# 5853-top-board.net
KiCad netlist of a schematic drawn in EAGLE
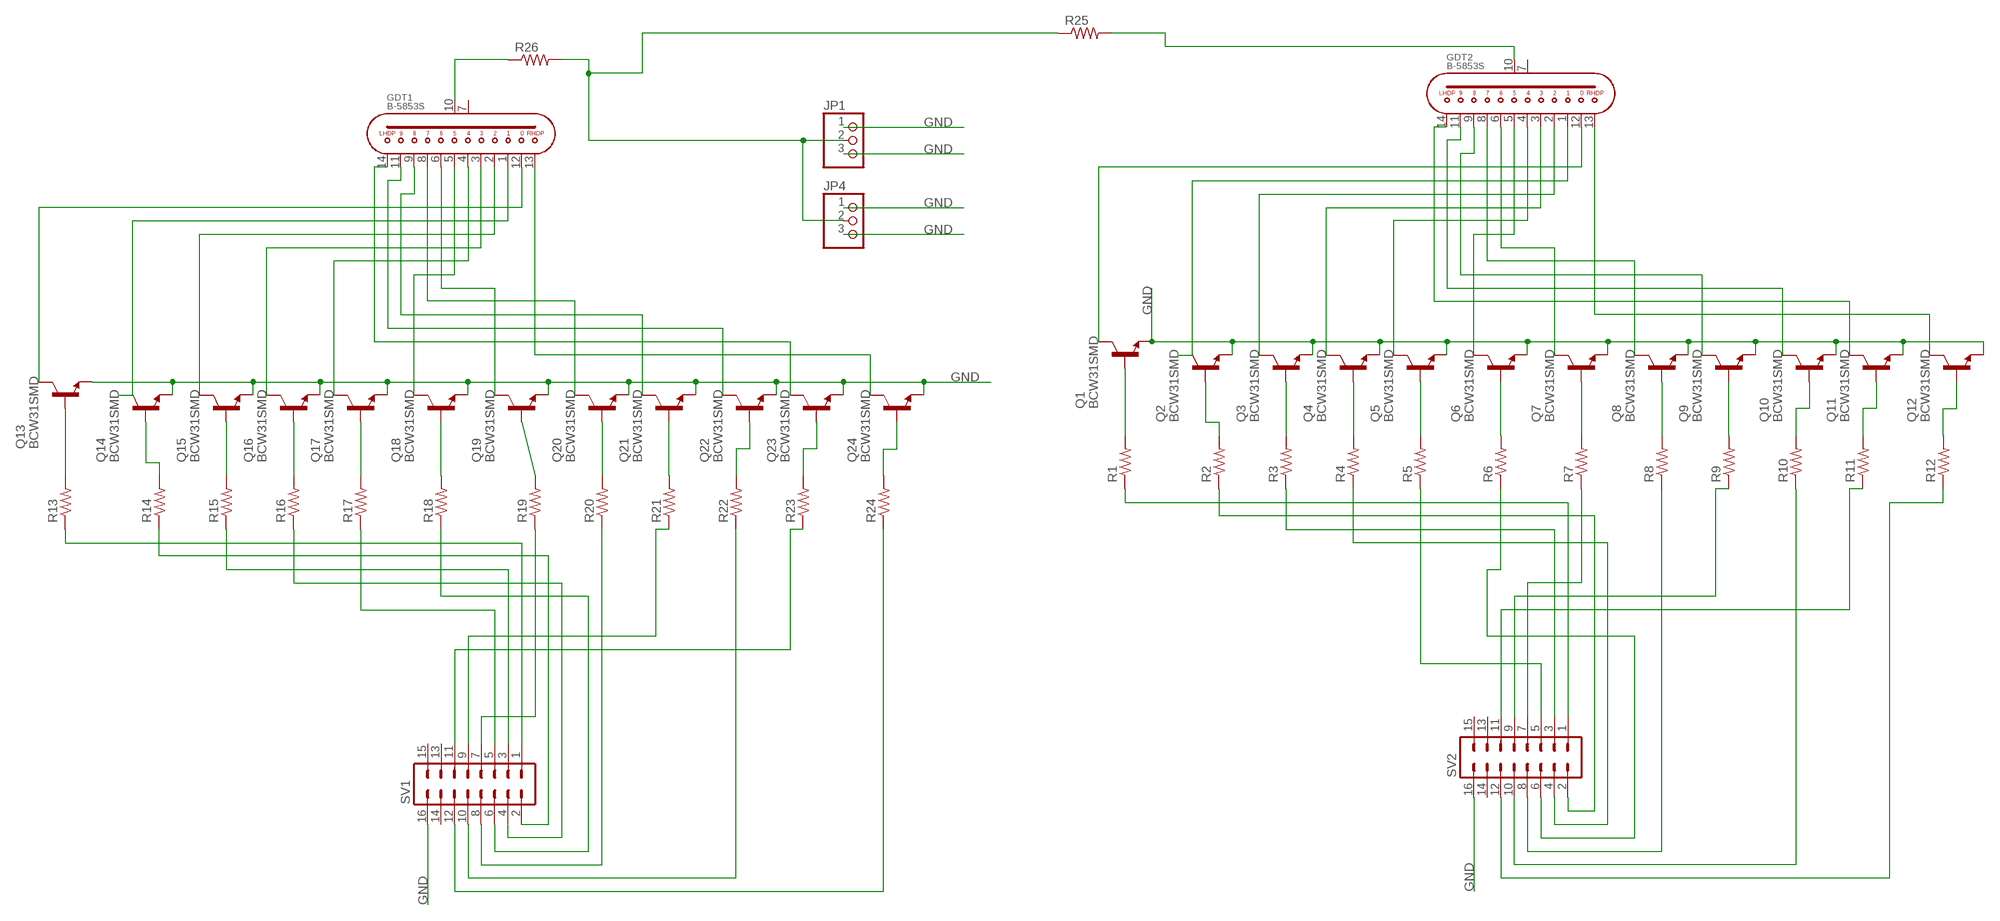
[diagram p0: schematic, sheet 1]

(export (version "E")
  (design (tool "Eeschema 10.0.6"))
  (components
    (comp (ref "GDT1")
      (value "B-5853S")
      (footprint "eagle-import:SK-207")
      (libsource (lib "eagle-import") (part "B-5853S"))
    )
    (comp (ref "GDT2")
      (value "B-5853S")
      (footprint "eagle-import:SK-207")
      (libsource (lib "eagle-import") (part "B-5853S"))
    )
    (comp (ref "JP1")
      (value "PINHD-1X3")
      (footprint "eagle-import:1X03")
      (libsource (lib "eagle-import") (part "PINHD-1X3"))
    )
    (comp (ref "JP4")
      (value "PINHD-1X3")
      (footprint "eagle-import:1X03")
      (libsource (lib "eagle-import") (part "PINHD-1X3"))
    )
    (comp (ref "Q1")
      (value "BCW31SMD")
      (footprint "eagle-import:SOT23-BEC")
      (libsource (lib "eagle-import") (part "BCW31SMD"))
    )
    (comp (ref "Q2")
      (value "BCW31SMD")
      (footprint "eagle-import:SOT23-BEC")
      (libsource (lib "eagle-import") (part "BCW31SMD"))
    )
    (comp (ref "Q3")
      (value "BCW31SMD")
      (footprint "eagle-import:SOT23-BEC")
      (libsource (lib "eagle-import") (part "BCW31SMD"))
    )
    (comp (ref "Q4")
      (value "BCW31SMD")
      (footprint "eagle-import:SOT23-BEC")
      (libsource (lib "eagle-import") (part "BCW31SMD"))
    )
    (comp (ref "Q5")
      (value "BCW31SMD")
      (footprint "eagle-import:SOT23-BEC")
      (libsource (lib "eagle-import") (part "BCW31SMD"))
    )
    (comp (ref "Q6")
      (value "BCW31SMD")
      (footprint "eagle-import:SOT23-BEC")
      (libsource (lib "eagle-import") (part "BCW31SMD"))
    )
    (comp (ref "Q7")
      (value "BCW31SMD")
      (footprint "eagle-import:SOT23-BEC")
      (libsource (lib "eagle-import") (part "BCW31SMD"))
    )
    (comp (ref "Q8")
      (value "BCW31SMD")
      (footprint "eagle-import:SOT23-BEC")
      (libsource (lib "eagle-import") (part "BCW31SMD"))
    )
    (comp (ref "Q9")
      (value "BCW31SMD")
      (footprint "eagle-import:SOT23-BEC")
      (libsource (lib "eagle-import") (part "BCW31SMD"))
    )
    (comp (ref "Q10")
      (value "BCW31SMD")
      (footprint "eagle-import:SOT23-BEC")
      (libsource (lib "eagle-import") (part "BCW31SMD"))
    )
    (comp (ref "Q11")
      (value "BCW31SMD")
      (footprint "eagle-import:SOT23-BEC")
      (libsource (lib "eagle-import") (part "BCW31SMD"))
    )
    (comp (ref "Q12")
      (value "BCW31SMD")
      (footprint "eagle-import:SOT23-BEC")
      (libsource (lib "eagle-import") (part "BCW31SMD"))
    )
    (comp (ref "Q13")
      (value "BCW31SMD")
      (footprint "eagle-import:SOT23-BEC")
      (libsource (lib "eagle-import") (part "BCW31SMD"))
    )
    (comp (ref "Q14")
      (value "BCW31SMD")
      (footprint "eagle-import:SOT23-BEC")
      (libsource (lib "eagle-import") (part "BCW31SMD"))
    )
    (comp (ref "Q15")
      (value "BCW31SMD")
      (footprint "eagle-import:SOT23-BEC")
      (libsource (lib "eagle-import") (part "BCW31SMD"))
    )
    (comp (ref "Q16")
      (value "BCW31SMD")
      (footprint "eagle-import:SOT23-BEC")
      (libsource (lib "eagle-import") (part "BCW31SMD"))
    )
    (comp (ref "Q17")
      (value "BCW31SMD")
      (footprint "eagle-import:SOT23-BEC")
      (libsource (lib "eagle-import") (part "BCW31SMD"))
    )
    (comp (ref "Q18")
      (value "BCW31SMD")
      (footprint "eagle-import:SOT23-BEC")
      (libsource (lib "eagle-import") (part "BCW31SMD"))
    )
    (comp (ref "Q19")
      (value "BCW31SMD")
      (footprint "eagle-import:SOT23-BEC")
      (libsource (lib "eagle-import") (part "BCW31SMD"))
    )
    (comp (ref "Q20")
      (value "BCW31SMD")
      (footprint "eagle-import:SOT23-BEC")
      (libsource (lib "eagle-import") (part "BCW31SMD"))
    )
    (comp (ref "Q21")
      (value "BCW31SMD")
      (footprint "eagle-import:SOT23-BEC")
      (libsource (lib "eagle-import") (part "BCW31SMD"))
    )
    (comp (ref "Q22")
      (value "BCW31SMD")
      (footprint "eagle-import:SOT23-BEC")
      (libsource (lib "eagle-import") (part "BCW31SMD"))
    )
    (comp (ref "Q23")
      (value "BCW31SMD")
      (footprint "eagle-import:SOT23-BEC")
      (libsource (lib "eagle-import") (part "BCW31SMD"))
    )
    (comp (ref "Q24")
      (value "BCW31SMD")
      (footprint "eagle-import:SOT23-BEC")
      (libsource (lib "eagle-import") (part "BCW31SMD"))
    )
    (comp (ref "R1")
      (value "R-US_M0805")
      (footprint "eagle-import:M0805")
      (libsource (lib "eagle-import") (part "R-US_M0805"))
    )
    (comp (ref "R2")
      (value "R-US_M0805")
      (footprint "eagle-import:M0805")
      (libsource (lib "eagle-import") (part "R-US_M0805"))
    )
    (comp (ref "R3")
      (value "R-US_M0805")
      (footprint "eagle-import:M0805")
      (libsource (lib "eagle-import") (part "R-US_M0805"))
    )
    (comp (ref "R4")
      (value "R-US_M0805")
      (footprint "eagle-import:M0805")
      (libsource (lib "eagle-import") (part "R-US_M0805"))
    )
    (comp (ref "R5")
      (value "R-US_M0805")
      (footprint "eagle-import:M0805")
      (libsource (lib "eagle-import") (part "R-US_M0805"))
    )
    (comp (ref "R6")
      (value "R-US_M0805")
      (footprint "eagle-import:M0805")
      (libsource (lib "eagle-import") (part "R-US_M0805"))
    )
    (comp (ref "R7")
      (value "R-US_M0805")
      (footprint "eagle-import:M0805")
      (libsource (lib "eagle-import") (part "R-US_M0805"))
    )
    (comp (ref "R8")
      (value "R-US_M0805")
      (footprint "eagle-import:M0805")
      (libsource (lib "eagle-import") (part "R-US_M0805"))
    )
    (comp (ref "R9")
      (value "R-US_M0805")
      (footprint "eagle-import:M0805")
      (libsource (lib "eagle-import") (part "R-US_M0805"))
    )
    (comp (ref "R10")
      (value "R-US_M0805")
      (footprint "eagle-import:M0805")
      (libsource (lib "eagle-import") (part "R-US_M0805"))
    )
    (comp (ref "R11")
      (value "R-US_M0805")
      (footprint "eagle-import:M0805")
      (libsource (lib "eagle-import") (part "R-US_M0805"))
    )
    (comp (ref "R12")
      (value "R-US_M0805")
      (footprint "eagle-import:M0805")
      (libsource (lib "eagle-import") (part "R-US_M0805"))
    )
    (comp (ref "R13")
      (value "R-US_M0805")
      (footprint "eagle-import:M0805")
      (libsource (lib "eagle-import") (part "R-US_M0805"))
    )
    (comp (ref "R14")
      (value "R-US_M0805")
      (footprint "eagle-import:M0805")
      (libsource (lib "eagle-import") (part "R-US_M0805"))
    )
    (comp (ref "R15")
      (value "R-US_M0805")
      (footprint "eagle-import:M0805")
      (libsource (lib "eagle-import") (part "R-US_M0805"))
    )
    (comp (ref "R16")
      (value "R-US_M0805")
      (footprint "eagle-import:M0805")
      (libsource (lib "eagle-import") (part "R-US_M0805"))
    )
    (comp (ref "R17")
      (value "R-US_M0805")
      (footprint "eagle-import:M0805")
      (libsource (lib "eagle-import") (part "R-US_M0805"))
    )
    (comp (ref "R18")
      (value "R-US_M0805")
      (footprint "eagle-import:M0805")
      (libsource (lib "eagle-import") (part "R-US_M0805"))
    )
    (comp (ref "R19")
      (value "R-US_M0805")
      (footprint "eagle-import:M0805")
      (libsource (lib "eagle-import") (part "R-US_M0805"))
    )
    (comp (ref "R20")
      (value "R-US_M0805")
      (footprint "eagle-import:M0805")
      (libsource (lib "eagle-import") (part "R-US_M0805"))
    )
    (comp (ref "R21")
      (value "R-US_M0805")
      (footprint "eagle-import:M0805")
      (libsource (lib "eagle-import") (part "R-US_M0805"))
    )
    (comp (ref "R22")
      (value "R-US_M0805")
      (footprint "eagle-import:M0805")
      (libsource (lib "eagle-import") (part "R-US_M0805"))
    )
    (comp (ref "R23")
      (value "R-US_M0805")
      (footprint "eagle-import:M0805")
      (libsource (lib "eagle-import") (part "R-US_M0805"))
    )
    (comp (ref "R24")
      (value "R-US_M0805")
      (footprint "eagle-import:M0805")
      (libsource (lib "eagle-import") (part "R-US_M0805"))
    )
    (comp (ref "R25")
      (value "R-US_M0805")
      (footprint "eagle-import:M0805")
      (libsource (lib "eagle-import") (part "R-US_M0805"))
    )
    (comp (ref "R26")
      (value "R-US_M0805")
      (footprint "eagle-import:M0805")
      (libsource (lib "eagle-import") (part "R-US_M0805"))
    )
    (comp (ref "SV1")
      (value "ML16")
      (footprint "eagle-import:ML16")
      (libsource (lib "eagle-import") (part "ML16"))
    )
    (comp (ref "SV2")
      (value "ML16")
      (footprint "eagle-import:ML16")
      (libsource (lib "eagle-import") (part "ML16"))
    )
  )
  (nets
    (net (code "1") (name "/GND") (class "Default")
      (node (ref "JP1") (pin "1") (pinfunction "1_1") (pintype "passive"))
      (node (ref "JP1") (pin "3") (pinfunction "3_3") (pintype "passive"))
      (node (ref "JP4") (pin "1") (pinfunction "1_1") (pintype "passive"))
      (node (ref "JP4") (pin "3") (pinfunction "3_3") (pintype "passive"))
      (node (ref "Q1") (pin "E") (pinfunction "E_E") (pintype "passive"))
      (node (ref "Q10") (pin "E") (pinfunction "E_E") (pintype "passive"))
      (node (ref "Q11") (pin "E") (pinfunction "E_E") (pintype "passive"))
      (node (ref "Q12") (pin "E") (pinfunction "E_E") (pintype "passive"))
      (node (ref "Q13") (pin "E") (pinfunction "E_E") (pintype "passive"))
      (node (ref "Q14") (pin "E") (pinfunction "E_E") (pintype "passive"))
      (node (ref "Q15") (pin "E") (pinfunction "E_E") (pintype "passive"))
      (node (ref "Q16") (pin "E") (pinfunction "E_E") (pintype "passive"))
      (node (ref "Q17") (pin "E") (pinfunction "E_E") (pintype "passive"))
      (node (ref "Q18") (pin "E") (pinfunction "E_E") (pintype "passive"))
      (node (ref "Q19") (pin "E") (pinfunction "E_E") (pintype "passive"))
      (node (ref "Q2") (pin "E") (pinfunction "E_E") (pintype "passive"))
      (node (ref "Q20") (pin "E") (pinfunction "E_E") (pintype "passive"))
      (node (ref "Q21") (pin "E") (pinfunction "E_E") (pintype "passive"))
      (node (ref "Q22") (pin "E") (pinfunction "E_E") (pintype "passive"))
      (node (ref "Q23") (pin "E") (pinfunction "E_E") (pintype "passive"))
      (node (ref "Q24") (pin "E") (pinfunction "E_E") (pintype "passive"))
      (node (ref "Q3") (pin "E") (pinfunction "E_E") (pintype "passive"))
      (node (ref "Q4") (pin "E") (pinfunction "E_E") (pintype "passive"))
      (node (ref "Q5") (pin "E") (pinfunction "E_E") (pintype "passive"))
      (node (ref "Q6") (pin "E") (pinfunction "E_E") (pintype "passive"))
      (node (ref "Q7") (pin "E") (pinfunction "E_E") (pintype "passive"))
      (node (ref "Q8") (pin "E") (pinfunction "E_E") (pintype "passive"))
      (node (ref "Q9") (pin "E") (pinfunction "E_E") (pintype "passive"))
      (node (ref "SV1") (pin "16") (pinfunction "16_16") (pintype "passive"))
      (node (ref "SV2") (pin "16") (pinfunction "16_16") (pintype "passive"))
    )
    (net (code "2") (name "Net-(GDT1-Pad1)") (class "Default")
      (node (ref "GDT1") (pin "1") (pinfunction "1_1") (pintype "passive"))
      (node (ref "Q14") (pin "C") (pinfunction "C_C") (pintype "passive"))
    )
    (net (code "3") (name "Net-(GDT1-Pad2)") (class "Default")
      (node (ref "GDT1") (pin "2") (pinfunction "2_2") (pintype "passive"))
      (node (ref "Q15") (pin "C") (pinfunction "C_C") (pintype "passive"))
    )
    (net (code "4") (name "Net-(GDT1-Pad3)") (class "Default")
      (node (ref "GDT1") (pin "3") (pinfunction "3_3") (pintype "passive"))
      (node (ref "Q16") (pin "C") (pinfunction "C_C") (pintype "passive"))
    )
    (net (code "5") (name "Net-(GDT1-Pad4)") (class "Default")
      (node (ref "GDT1") (pin "4") (pinfunction "4_4") (pintype "passive"))
      (node (ref "Q17") (pin "C") (pinfunction "C_C") (pintype "passive"))
    )
    (net (code "6") (name "Net-(GDT1-Pad5)") (class "Default")
      (node (ref "GDT1") (pin "5") (pinfunction "5_5") (pintype "passive"))
      (node (ref "Q18") (pin "C") (pinfunction "C_C") (pintype "passive"))
    )
    (net (code "7") (name "Net-(GDT1-Pad6)") (class "Default")
      (node (ref "GDT1") (pin "6") (pinfunction "6_6") (pintype "passive"))
      (node (ref "Q19") (pin "C") (pinfunction "C_C") (pintype "passive"))
    )
    (net (code "8") (name "Net-(GDT1-Pad8)") (class "Default")
      (node (ref "GDT1") (pin "8") (pinfunction "8_8") (pintype "passive"))
      (node (ref "Q20") (pin "C") (pinfunction "C_C") (pintype "passive"))
    )
    (net (code "9") (name "Net-(GDT1-Pad9)") (class "Default")
      (node (ref "GDT1") (pin "9") (pinfunction "9_9") (pintype "passive"))
      (node (ref "Q21") (pin "C") (pinfunction "C_C") (pintype "passive"))
    )
    (net (code "10") (name "Net-(GDT1-Pad10)") (class "Default")
      (node (ref "GDT1") (pin "10") (pinfunction "10_10") (pintype "passive"))
      (node (ref "R26") (pin "1") (pinfunction "1_1") (pintype "passive"))
    )
    (net (code "11") (name "Net-(GDT1-Pad11)") (class "Default")
      (node (ref "GDT1") (pin "11") (pinfunction "11_11") (pintype "passive"))
      (node (ref "Q22") (pin "C") (pinfunction "C_C") (pintype "passive"))
    )
    (net (code "12") (name "Net-(GDT1-Pad12)") (class "Default")
      (node (ref "GDT1") (pin "12") (pinfunction "12_12") (pintype "passive"))
      (node (ref "Q13") (pin "C") (pinfunction "C_C") (pintype "passive"))
    )
    (net (code "13") (name "Net-(GDT1-Pad13)") (class "Default")
      (node (ref "GDT1") (pin "13") (pinfunction "13_13") (pintype "passive"))
      (node (ref "Q24") (pin "C") (pinfunction "C_C") (pintype "passive"))
    )
    (net (code "14") (name "Net-(GDT1-Pad14)") (class "Default")
      (node (ref "GDT1") (pin "14") (pinfunction "14_14") (pintype "passive"))
      (node (ref "Q23") (pin "C") (pinfunction "C_C") (pintype "passive"))
    )
    (net (code "15") (name "Net-(GDT2-Pad1)") (class "Default")
      (node (ref "GDT2") (pin "1") (pinfunction "1_1") (pintype "passive"))
      (node (ref "Q2") (pin "C") (pinfunction "C_C") (pintype "passive"))
    )
    (net (code "16") (name "Net-(GDT2-Pad2)") (class "Default")
      (node (ref "GDT2") (pin "2") (pinfunction "2_2") (pintype "passive"))
      (node (ref "Q3") (pin "C") (pinfunction "C_C") (pintype "passive"))
    )
    (net (code "17") (name "Net-(GDT2-Pad3)") (class "Default")
      (node (ref "GDT2") (pin "3") (pinfunction "3_3") (pintype "passive"))
      (node (ref "Q4") (pin "C") (pinfunction "C_C") (pintype "passive"))
    )
    (net (code "18") (name "Net-(GDT2-Pad4)") (class "Default")
      (node (ref "GDT2") (pin "4") (pinfunction "4_4") (pintype "passive"))
      (node (ref "Q5") (pin "C") (pinfunction "C_C") (pintype "passive"))
    )
    (net (code "19") (name "Net-(GDT2-Pad5)") (class "Default")
      (node (ref "GDT2") (pin "5") (pinfunction "5_5") (pintype "passive"))
      (node (ref "Q6") (pin "C") (pinfunction "C_C") (pintype "passive"))
    )
    (net (code "20") (name "Net-(GDT2-Pad6)") (class "Default")
      (node (ref "GDT2") (pin "6") (pinfunction "6_6") (pintype "passive"))
      (node (ref "Q7") (pin "C") (pinfunction "C_C") (pintype "passive"))
    )
    (net (code "21") (name "Net-(GDT2-Pad8)") (class "Default")
      (node (ref "GDT2") (pin "8") (pinfunction "8_8") (pintype "passive"))
      (node (ref "Q8") (pin "C") (pinfunction "C_C") (pintype "passive"))
    )
    (net (code "22") (name "Net-(GDT2-Pad9)") (class "Default")
      (node (ref "GDT2") (pin "9") (pinfunction "9_9") (pintype "passive"))
      (node (ref "Q9") (pin "C") (pinfunction "C_C") (pintype "passive"))
    )
    (net (code "23") (name "Net-(GDT2-Pad10)") (class "Default")
      (node (ref "GDT2") (pin "10") (pinfunction "10_10") (pintype "passive"))
      (node (ref "R25") (pin "2") (pinfunction "2_2") (pintype "passive"))
    )
    (net (code "24") (name "Net-(GDT2-Pad11)") (class "Default")
      (node (ref "GDT2") (pin "11") (pinfunction "11_11") (pintype "passive"))
      (node (ref "Q10") (pin "C") (pinfunction "C_C") (pintype "passive"))
    )
    (net (code "25") (name "Net-(GDT2-Pad12)") (class "Default")
      (node (ref "GDT2") (pin "12") (pinfunction "12_12") (pintype "passive"))
      (node (ref "Q1") (pin "C") (pinfunction "C_C") (pintype "passive"))
    )
    (net (code "26") (name "Net-(GDT2-Pad13)") (class "Default")
      (node (ref "GDT2") (pin "13") (pinfunction "13_13") (pintype "passive"))
      (node (ref "Q12") (pin "C") (pinfunction "C_C") (pintype "passive"))
    )
    (net (code "27") (name "Net-(GDT2-Pad14)") (class "Default")
      (node (ref "GDT2") (pin "14") (pinfunction "14_14") (pintype "passive"))
      (node (ref "Q11") (pin "C") (pinfunction "C_C") (pintype "passive"))
    )
    (net (code "28") (name "Net-(JP1-Pad2)") (class "Default")
      (node (ref "JP1") (pin "2") (pinfunction "2_2") (pintype "passive"))
      (node (ref "JP4") (pin "2") (pinfunction "2_2") (pintype "passive"))
      (node (ref "R25") (pin "1") (pinfunction "1_1") (pintype "passive"))
      (node (ref "R26") (pin "2") (pinfunction "2_2") (pintype "passive"))
    )
    (net (code "29") (name "Net-(Q1-PadB)") (class "Default")
      (node (ref "Q1") (pin "B") (pinfunction "B_B") (pintype "passive"))
      (node (ref "R1") (pin "2") (pinfunction "2_2") (pintype "passive"))
    )
    (net (code "30") (name "Net-(Q2-PadB)") (class "Default")
      (node (ref "Q2") (pin "B") (pinfunction "B_B") (pintype "passive"))
      (node (ref "R2") (pin "2") (pinfunction "2_2") (pintype "passive"))
    )
    (net (code "31") (name "Net-(Q3-PadB)") (class "Default")
      (node (ref "Q3") (pin "B") (pinfunction "B_B") (pintype "passive"))
      (node (ref "R3") (pin "2") (pinfunction "2_2") (pintype "passive"))
    )
    (net (code "32") (name "Net-(Q4-PadB)") (class "Default")
      (node (ref "Q4") (pin "B") (pinfunction "B_B") (pintype "passive"))
      (node (ref "R4") (pin "2") (pinfunction "2_2") (pintype "passive"))
    )
    (net (code "33") (name "Net-(Q5-PadB)") (class "Default")
      (node (ref "Q5") (pin "B") (pinfunction "B_B") (pintype "passive"))
      (node (ref "R5") (pin "2") (pinfunction "2_2") (pintype "passive"))
    )
    (net (code "34") (name "Net-(Q6-PadB)") (class "Default")
      (node (ref "Q6") (pin "B") (pinfunction "B_B") (pintype "passive"))
      (node (ref "R6") (pin "2") (pinfunction "2_2") (pintype "passive"))
    )
    (net (code "35") (name "Net-(Q7-PadB)") (class "Default")
      (node (ref "Q7") (pin "B") (pinfunction "B_B") (pintype "passive"))
      (node (ref "R7") (pin "2") (pinfunction "2_2") (pintype "passive"))
    )
    (net (code "36") (name "Net-(Q8-PadB)") (class "Default")
      (node (ref "Q8") (pin "B") (pinfunction "B_B") (pintype "passive"))
      (node (ref "R8") (pin "2") (pinfunction "2_2") (pintype "passive"))
    )
    (net (code "37") (name "Net-(Q9-PadB)") (class "Default")
      (node (ref "Q9") (pin "B") (pinfunction "B_B") (pintype "passive"))
      (node (ref "R9") (pin "2") (pinfunction "2_2") (pintype "passive"))
    )
    (net (code "38") (name "Net-(Q10-PadB)") (class "Default")
      (node (ref "Q10") (pin "B") (pinfunction "B_B") (pintype "passive"))
      (node (ref "R10") (pin "2") (pinfunction "2_2") (pintype "passive"))
    )
    (net (code "39") (name "Net-(Q11-PadB)") (class "Default")
      (node (ref "Q11") (pin "B") (pinfunction "B_B") (pintype "passive"))
      (node (ref "R11") (pin "2") (pinfunction "2_2") (pintype "passive"))
    )
    (net (code "40") (name "Net-(Q12-PadB)") (class "Default")
      (node (ref "Q12") (pin "B") (pinfunction "B_B") (pintype "passive"))
      (node (ref "R12") (pin "2") (pinfunction "2_2") (pintype "passive"))
    )
    (net (code "41") (name "Net-(Q13-PadB)") (class "Default")
      (node (ref "Q13") (pin "B") (pinfunction "B_B") (pintype "passive"))
      (node (ref "R13") (pin "2") (pinfunction "2_2") (pintype "passive"))
    )
    (net (code "42") (name "Net-(Q14-PadB)") (class "Default")
      (node (ref "Q14") (pin "B") (pinfunction "B_B") (pintype "passive"))
      (node (ref "R14") (pin "2") (pinfunction "2_2") (pintype "passive"))
    )
    (net (code "43") (name "Net-(Q15-PadB)") (class "Default")
      (node (ref "Q15") (pin "B") (pinfunction "B_B") (pintype "passive"))
      (node (ref "R15") (pin "2") (pinfunction "2_2") (pintype "passive"))
    )
    (net (code "44") (name "Net-(Q16-PadB)") (class "Default")
      (node (ref "Q16") (pin "B") (pinfunction "B_B") (pintype "passive"))
      (node (ref "R16") (pin "2") (pinfunction "2_2") (pintype "passive"))
    )
    (net (code "45") (name "Net-(Q17-PadB)") (class "Default")
      (node (ref "Q17") (pin "B") (pinfunction "B_B") (pintype "passive"))
      (node (ref "R17") (pin "2") (pinfunction "2_2") (pintype "passive"))
    )
    (net (code "46") (name "Net-(Q18-PadB)") (class "Default")
      (node (ref "Q18") (pin "B") (pinfunction "B_B") (pintype "passive"))
      (node (ref "R18") (pin "2") (pinfunction "2_2") (pintype "passive"))
    )
    (net (code "47") (name "Net-(Q19-PadB)") (class "Default")
      (node (ref "Q19") (pin "B") (pinfunction "B_B") (pintype "passive"))
      (node (ref "R19") (pin "2") (pinfunction "2_2") (pintype "passive"))
    )
    (net (code "48") (name "Net-(Q20-PadB)") (class "Default")
      (node (ref "Q20") (pin "B") (pinfunction "B_B") (pintype "passive"))
      (node (ref "R20") (pin "2") (pinfunction "2_2") (pintype "passive"))
    )
    (net (code "49") (name "Net-(Q21-PadB)") (class "Default")
      (node (ref "Q21") (pin "B") (pinfunction "B_B") (pintype "passive"))
      (node (ref "R21") (pin "2") (pinfunction "2_2") (pintype "passive"))
    )
    (net (code "50") (name "Net-(Q22-PadB)") (class "Default")
      (node (ref "Q22") (pin "B") (pinfunction "B_B") (pintype "passive"))
      (node (ref "R22") (pin "2") (pinfunction "2_2") (pintype "passive"))
    )
    (net (code "51") (name "Net-(Q23-PadB)") (class "Default")
      (node (ref "Q23") (pin "B") (pinfunction "B_B") (pintype "passive"))
      (node (ref "R23") (pin "2") (pinfunction "2_2") (pintype "passive"))
    )
    (net (code "52") (name "Net-(Q24-PadB)") (class "Default")
      (node (ref "Q24") (pin "B") (pinfunction "B_B") (pintype "passive"))
      (node (ref "R24") (pin "2") (pinfunction "2_2") (pintype "passive"))
    )
    (net (code "53") (name "Net-(R1-Pad1)") (class "Default")
      (node (ref "R1") (pin "1") (pinfunction "1_1") (pintype "passive"))
      (node (ref "SV2") (pin "1") (pinfunction "1_1") (pintype "passive"))
    )
    (net (code "54") (name "Net-(R2-Pad1)") (class "Default")
      (node (ref "R2") (pin "1") (pinfunction "1_1") (pintype "passive"))
      (node (ref "SV2") (pin "2") (pinfunction "2_2") (pintype "passive"))
    )
    (net (code "55") (name "Net-(R3-Pad1)") (class "Default")
      (node (ref "R3") (pin "1") (pinfunction "1_1") (pintype "passive"))
      (node (ref "SV2") (pin "3") (pinfunction "3_3") (pintype "passive"))
    )
    (net (code "56") (name "Net-(R4-Pad1)") (class "Default")
      (node (ref "R4") (pin "1") (pinfunction "1_1") (pintype "passive"))
      (node (ref "SV2") (pin "4") (pinfunction "4_4") (pintype "passive"))
    )
    (net (code "57") (name "Net-(R5-Pad1)") (class "Default")
      (node (ref "R5") (pin "1") (pinfunction "1_1") (pintype "passive"))
      (node (ref "SV2") (pin "5") (pinfunction "5_5") (pintype "passive"))
    )
    (net (code "58") (name "Net-(R6-Pad1)") (class "Default")
      (node (ref "R6") (pin "1") (pinfunction "1_1") (pintype "passive"))
      (node (ref "SV2") (pin "6") (pinfunction "6_6") (pintype "passive"))
    )
    (net (code "59") (name "Net-(R7-Pad1)") (class "Default")
      (node (ref "R7") (pin "1") (pinfunction "1_1") (pintype "passive"))
      (node (ref "SV2") (pin "7") (pinfunction "7_7") (pintype "passive"))
    )
    (net (code "60") (name "Net-(R8-Pad1)") (class "Default")
      (node (ref "R8") (pin "1") (pinfunction "1_1") (pintype "passive"))
      (node (ref "SV2") (pin "8") (pinfunction "8_8") (pintype "passive"))
    )
    (net (code "61") (name "Net-(R9-Pad1)") (class "Default")
      (node (ref "R9") (pin "1") (pinfunction "1_1") (pintype "passive"))
      (node (ref "SV2") (pin "9") (pinfunction "9_9") (pintype "passive"))
    )
    (net (code "62") (name "Net-(R10-Pad1)") (class "Default")
      (node (ref "R10") (pin "1") (pinfunction "1_1") (pintype "passive"))
      (node (ref "SV2") (pin "10") (pinfunction "10_10") (pintype "passive"))
    )
    (net (code "63") (name "Net-(R11-Pad1)") (class "Default")
      (node (ref "R11") (pin "1") (pinfunction "1_1") (pintype "passive"))
      (node (ref "SV2") (pin "11") (pinfunction "11_11") (pintype "passive"))
    )
    (net (code "64") (name "Net-(R12-Pad1)") (class "Default")
      (node (ref "R12") (pin "1") (pinfunction "1_1") (pintype "passive"))
      (node (ref "SV2") (pin "12") (pinfunction "12_12") (pintype "passive"))
    )
    (net (code "65") (name "Net-(R13-Pad1)") (class "Default")
      (node (ref "R13") (pin "1") (pinfunction "1_1") (pintype "passive"))
      (node (ref "SV1") (pin "1") (pinfunction "1_1") (pintype "passive"))
    )
    (net (code "66") (name "Net-(R14-Pad1)") (class "Default")
      (node (ref "R14") (pin "1") (pinfunction "1_1") (pintype "passive"))
      (node (ref "SV1") (pin "2") (pinfunction "2_2") (pintype "passive"))
    )
    (net (code "67") (name "Net-(R15-Pad1)") (class "Default")
      (node (ref "R15") (pin "1") (pinfunction "1_1") (pintype "passive"))
      (node (ref "SV1") (pin "3") (pinfunction "3_3") (pintype "passive"))
    )
    (net (code "68") (name "Net-(R16-Pad1)") (class "Default")
      (node (ref "R16") (pin "1") (pinfunction "1_1") (pintype "passive"))
      (node (ref "SV1") (pin "4") (pinfunction "4_4") (pintype "passive"))
    )
    (net (code "69") (name "Net-(R17-Pad1)") (class "Default")
      (node (ref "R17") (pin "1") (pinfunction "1_1") (pintype "passive"))
      (node (ref "SV1") (pin "5") (pinfunction "5_5") (pintype "passive"))
    )
    (net (code "70") (name "Net-(R18-Pad1)") (class "Default")
      (node (ref "R18") (pin "1") (pinfunction "1_1") (pintype "passive"))
      (node (ref "SV1") (pin "6") (pinfunction "6_6") (pintype "passive"))
    )
    (net (code "71") (name "Net-(R19-Pad1)") (class "Default")
      (node (ref "R19") (pin "1") (pinfunction "1_1") (pintype "passive"))
      (node (ref "SV1") (pin "7") (pinfunction "7_7") (pintype "passive"))
    )
    (net (code "72") (name "Net-(R20-Pad1)") (class "Default")
      (node (ref "R20") (pin "1") (pinfunction "1_1") (pintype "passive"))
      (node (ref "SV1") (pin "8") (pinfunction "8_8") (pintype "passive"))
    )
    (net (code "73") (name "Net-(R21-Pad1)") (class "Default")
      (node (ref "R21") (pin "1") (pinfunction "1_1") (pintype "passive"))
      (node (ref "SV1") (pin "9") (pinfunction "9_9") (pintype "passive"))
    )
    (net (code "74") (name "Net-(R22-Pad1)") (class "Default")
      (node (ref "R22") (pin "1") (pinfunction "1_1") (pintype "passive"))
      (node (ref "SV1") (pin "10") (pinfunction "10_10") (pintype "passive"))
    )
    (net (code "75") (name "Net-(R23-Pad1)") (class "Default")
      (node (ref "R23") (pin "1") (pinfunction "1_1") (pintype "passive"))
      (node (ref "SV1") (pin "11") (pinfunction "11_11") (pintype "passive"))
    )
    (net (code "76") (name "Net-(R24-Pad1)") (class "Default")
      (node (ref "R24") (pin "1") (pinfunction "1_1") (pintype "passive"))
      (node (ref "SV1") (pin "12") (pinfunction "12_12") (pintype "passive"))
    )
    (net (code "77") (name "unconnected-(GDT1-Pad7)") (class "Default")
      (node (ref "GDT1") (pin "7") (pinfunction "7_7") (pintype "passive"))
    )
    (net (code "78") (name "unconnected-(GDT2-Pad7)") (class "Default")
      (node (ref "GDT2") (pin "7") (pinfunction "7_7") (pintype "passive"))
    )
    (net (code "79") (name "unconnected-(SV1-Pad13)") (class "Default")
      (node (ref "SV1") (pin "13") (pinfunction "13_13") (pintype "passive"))
    )
    (net (code "80") (name "unconnected-(SV1-Pad14)") (class "Default")
      (node (ref "SV1") (pin "14") (pinfunction "14_14") (pintype "passive"))
    )
    (net (code "81") (name "unconnected-(SV1-Pad15)") (class "Default")
      (node (ref "SV1") (pin "15") (pinfunction "15_15") (pintype "passive"))
    )
    (net (code "82") (name "unconnected-(SV2-Pad13)") (class "Default")
      (node (ref "SV2") (pin "13") (pinfunction "13_13") (pintype "passive"))
    )
    (net (code "83") (name "unconnected-(SV2-Pad14)") (class "Default")
      (node (ref "SV2") (pin "14") (pinfunction "14_14") (pintype "passive"))
    )
    (net (code "84") (name "unconnected-(SV2-Pad15)") (class "Default")
      (node (ref "SV2") (pin "15") (pinfunction "15_15") (pintype "passive"))
    )
  )
)
